# old_line_kick.net
KiCad netlist of a schematic drawn in EAGLE
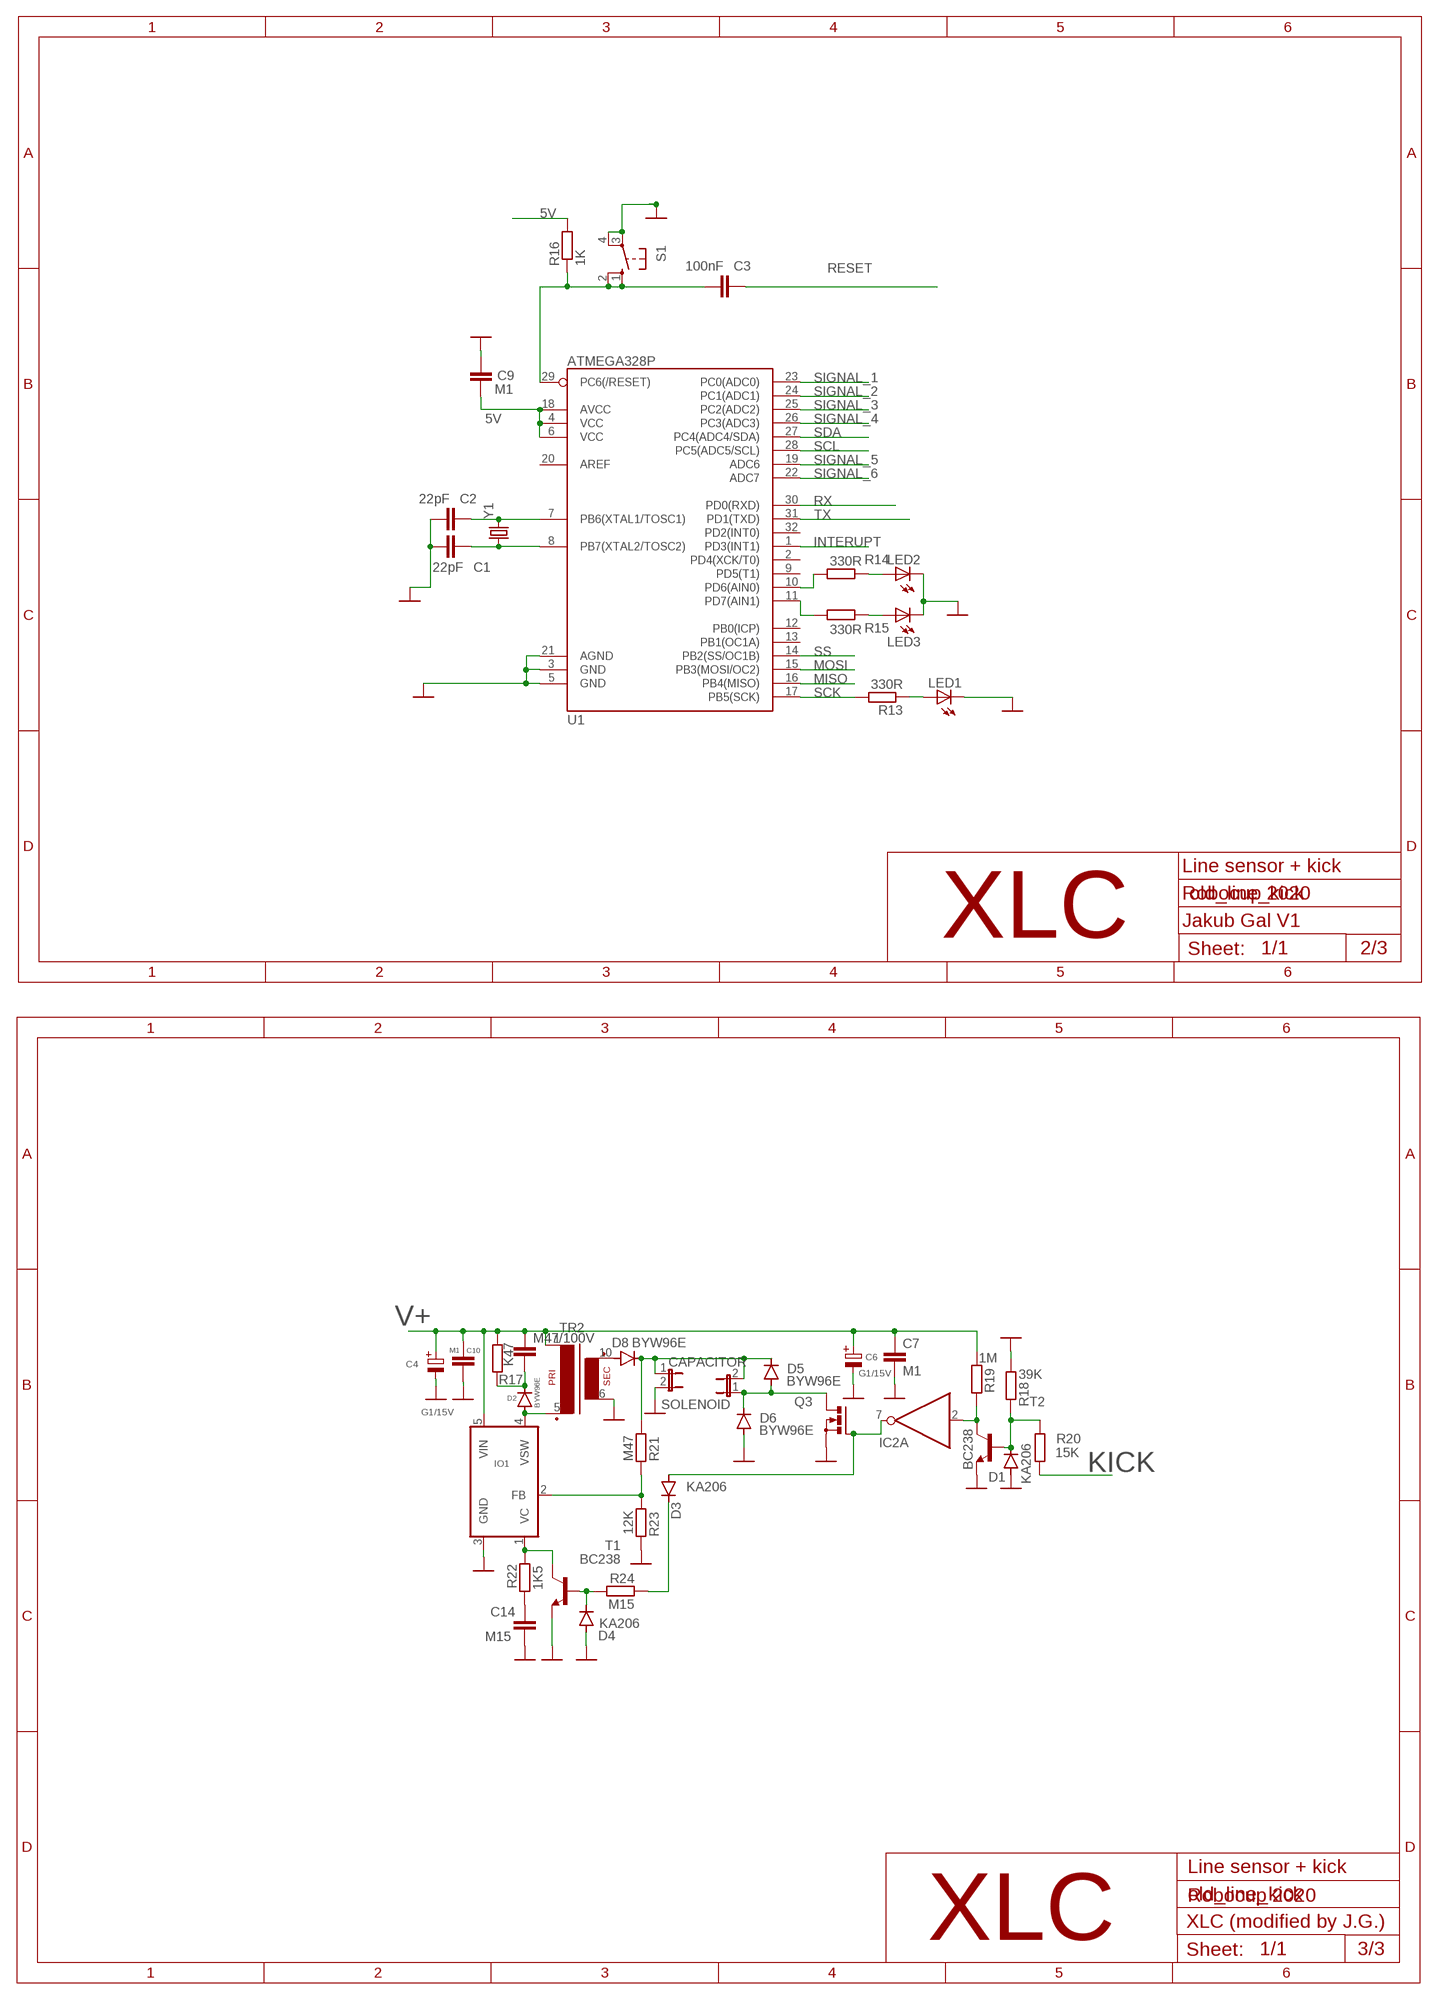
[diagram p0: schematic, sheet 1, part 1 of 2]
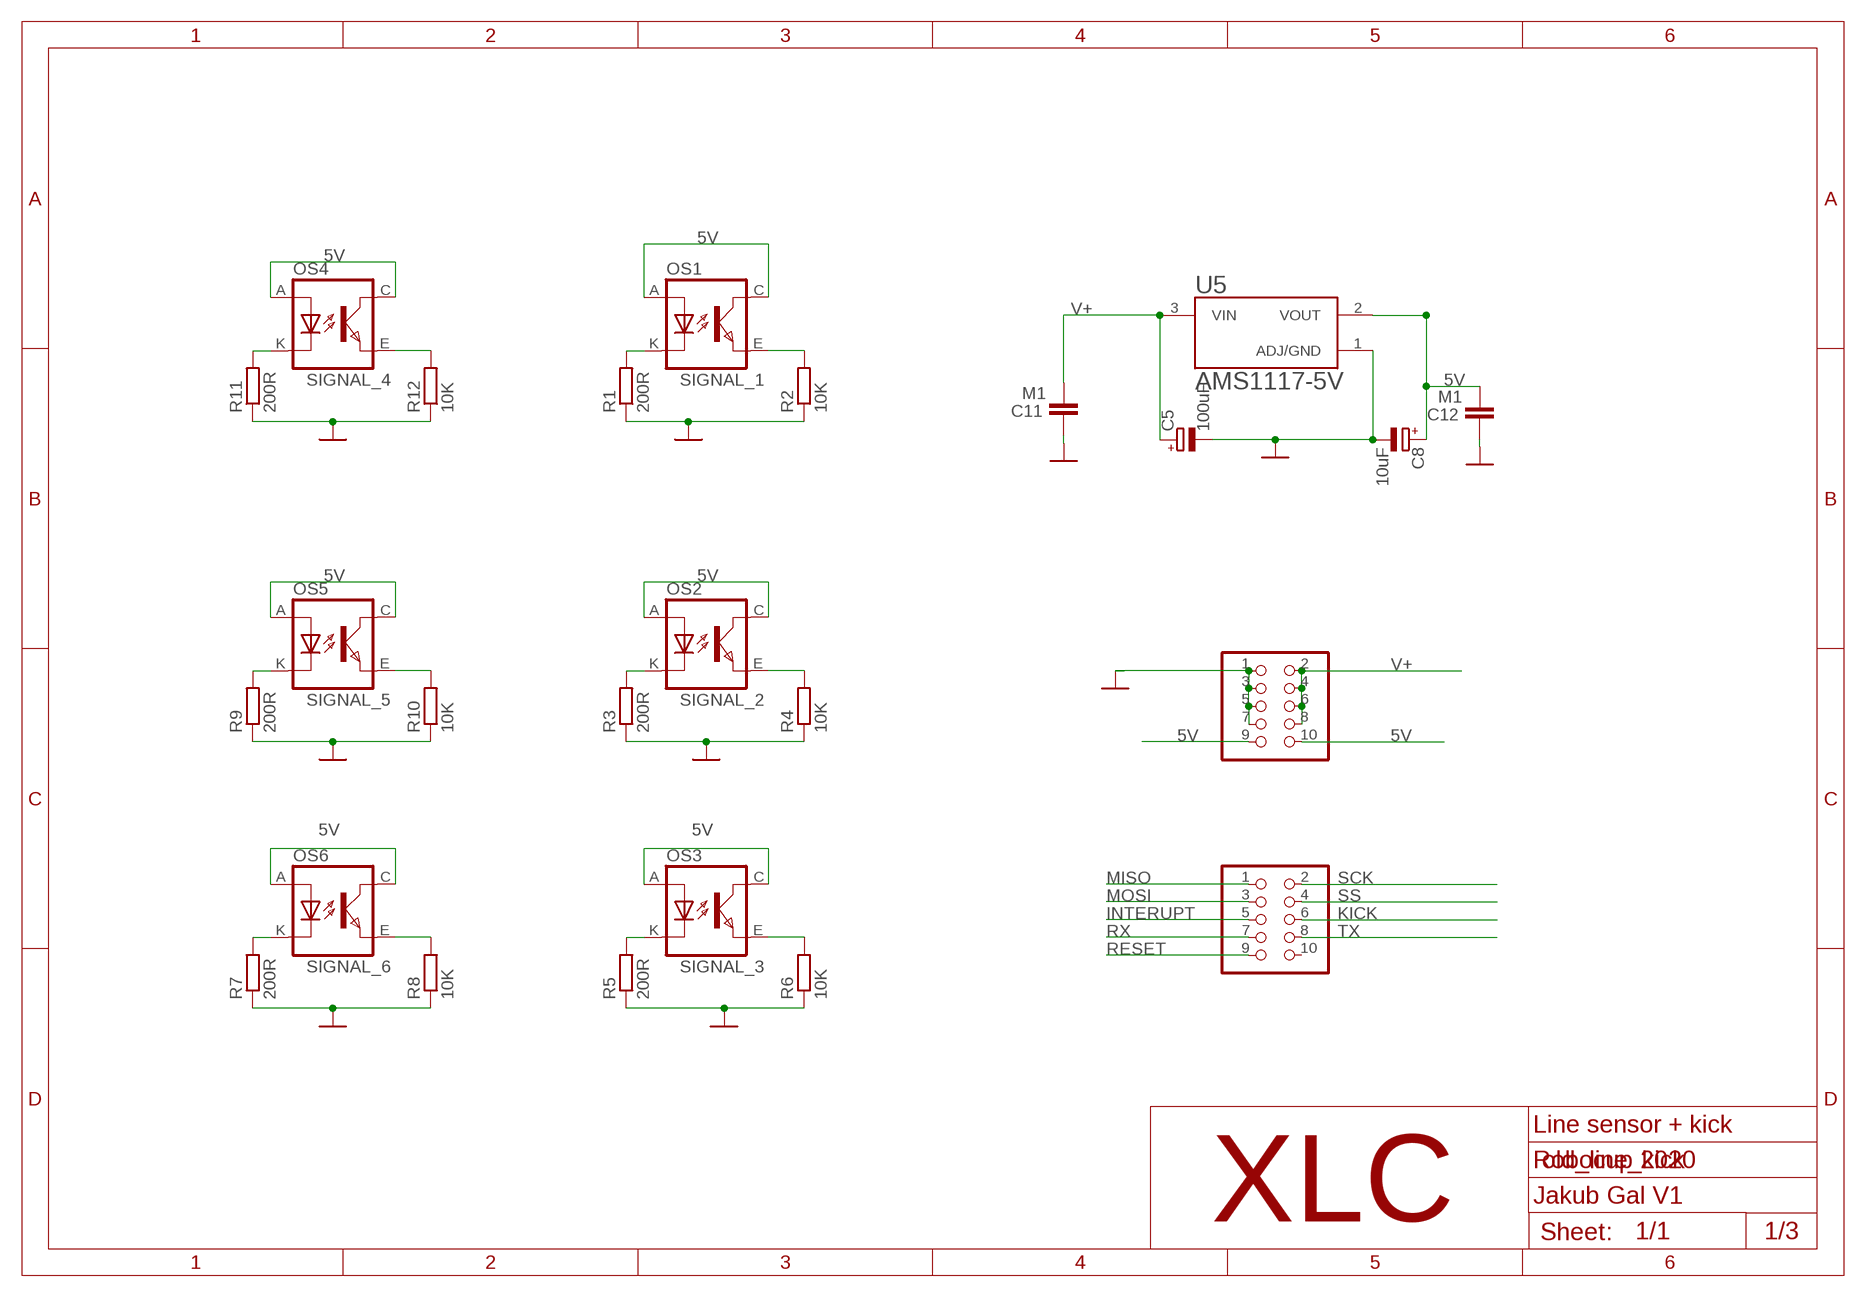
[diagram p1: schematic, sheet 1, part 2 of 2]

(export (version "E")
  (design (tool "Eeschema 10.0.6"))
  (components
    (comp (ref "C1")
      (value "22pF")
      (footprint "eagle-import:C0603")
      (libsource (lib "eagle-import") (part "C-EUC0603"))
    )
    (comp (ref "C2")
      (value "22pF")
      (footprint "eagle-import:C0603")
      (libsource (lib "eagle-import") (part "C-EUC0603"))
    )
    (comp (ref "C3")
      (value "100nF")
      (footprint "eagle-import:C0603")
      (libsource (lib "eagle-import") (part "C-EUC0603"))
    )
    (comp (ref "C4")
      (value "G1/15V")
      (footprint "eagle-import:E-2,5_7-RAD")
      (libsource (lib "eagle-import") (part "KOND-ELEKT-2,5/7"))
    )
    (comp (ref "C5")
      (value "100uF")
      (footprint "eagle-import:UD-6,3X7,7_NICHICON")
      (libsource (lib "eagle-import") (part "CPOL-EUUD-6,3X7,7"))
    )
    (comp (ref "C6")
      (value "G1/15V")
      (footprint "eagle-import:E-2,5_7-RAD")
      (libsource (lib "eagle-import") (part "KOND-ELEKT-2,5/7"))
    )
    (comp (ref "C7")
      (value "M1")
      (footprint "eagle-import:C0805K")
      (libsource (lib "eagle-import") (part "resistor_C-EUC0805K"))
    )
    (comp (ref "C8")
      (value "10uF")
      (footprint "eagle-import:UD-4X5,8_NICHICON")
      (libsource (lib "eagle-import") (part "CPOL-EUUD-4X5,8"))
    )
    (comp (ref "C9")
      (value "M1")
      (footprint "eagle-import:C0603")
      (libsource (lib "eagle-import") (part "C-EUC0603"))
    )
    (comp (ref "C10")
      (value "M1")
      (footprint "eagle-import:C0805K")
      (libsource (lib "eagle-import") (part "resistor_C-EUC0805K"))
    )
    (comp (ref "C11")
      (value "M1")
      (footprint "eagle-import:C0603")
      (libsource (lib "eagle-import") (part "C-EUC0603"))
    )
    (comp (ref "C12")
      (value "M1")
      (footprint "eagle-import:C0603")
      (libsource (lib "eagle-import") (part "C-EUC0603"))
    )
    (comp (ref "C14")
      (value "M15")
      (footprint "eagle-import:C0805K")
      (libsource (lib "eagle-import") (part "resistor_C-EUC0805K"))
    )
    (comp (ref "CAPACITOR")
      (value "JP1E")
      (footprint "eagle-import:JP1")
      (libsource (lib "eagle-import") (part "JP1E"))
    )
    (comp (ref "D1")
      (value "KA206")
      (footprint "eagle-import:D-7.5")
      (libsource (lib "eagle-import") (part "DIODE-D-7.5"))
    )
    (comp (ref "D2")
      (value "BYW96E")
      (footprint "eagle-import:SOD64-10")
      (libsource (lib "eagle-import") (part "BYW96"))
    )
    (comp (ref "D3")
      (value "KA206")
      (footprint "eagle-import:D-7.5")
      (libsource (lib "eagle-import") (part "DIODE-D-7.5"))
    )
    (comp (ref "D4")
      (value "KA206")
      (footprint "eagle-import:D-7.5")
      (libsource (lib "eagle-import") (part "DIODE-D-7.5"))
    )
    (comp (ref "D5")
      (value "BYW96E")
      (footprint "eagle-import:SOD64-10")
      (libsource (lib "eagle-import") (part "BYW96"))
    )
    (comp (ref "D6")
      (value "BYW96E")
      (footprint "eagle-import:SOD64-10")
      (libsource (lib "eagle-import") (part "BYW96"))
    )
    (comp (ref "D8")
      (value "BYW96E")
      (footprint "eagle-import:SOD64-10")
      (libsource (lib "eagle-import") (part "BYW96"))
    )
    (comp (ref "IC2")
      (value "MIC4423BM")
      (footprint "eagle-import:SO08")
      (libsource (lib "eagle-import") (part "MIC4423BM"))
    )
    (comp (ref "IO1")
      (value "LT1071V")
      (footprint "eagle-import:TO220-5P")
      (libsource (lib "eagle-import") (part "LT1071V"))
    )
    (comp (ref "JP2")
      (value "PINHD-2X5")
      (footprint "eagle-import:2X05")
      (libsource (lib "eagle-import") (part "PINHD-2X5"))
    )
    (comp (ref "JP3")
      (value "PINHD-2X5")
      (footprint "eagle-import:2X05")
      (libsource (lib "eagle-import") (part "PINHD-2X5"))
    )
    (comp (ref "LED1")
      (value "LEDCHIPLED_0603")
      (footprint "eagle-import:CHIPLED_0603")
      (libsource (lib "eagle-import") (part "LEDCHIPLED_0603"))
    )
    (comp (ref "LED2")
      (value "LEDCHIPLED_0603")
      (footprint "eagle-import:CHIPLED_0603")
      (libsource (lib "eagle-import") (part "LEDCHIPLED_0603"))
    )
    (comp (ref "LED3")
      (value "LEDCHIPLED_0603")
      (footprint "eagle-import:CHIPLED_0603")
      (libsource (lib "eagle-import") (part "LEDCHIPLED_0603"))
    )
    (comp (ref "M47/100V")
      (value "C-EUC0805K")
      (footprint "eagle-import:C0805K")
      (libsource (lib "eagle-import") (part "resistor_C-EUC0805K"))
    )
    (comp (ref "OS1")
      (value "TCRT5000")
      (footprint "eagle-import:TCRT5000")
      (libsource (lib "eagle-import") (part "TCRT5000"))
    )
    (comp (ref "OS2")
      (value "TCRT5000")
      (footprint "eagle-import:TCRT5000")
      (libsource (lib "eagle-import") (part "TCRT5000"))
    )
    (comp (ref "OS3")
      (value "TCRT5000")
      (footprint "eagle-import:TCRT5000")
      (libsource (lib "eagle-import") (part "TCRT5000"))
    )
    (comp (ref "OS4")
      (value "TCRT5000")
      (footprint "eagle-import:TCRT5000")
      (fields (field (name "SPICEPREFIX") "O"))
      (libsource (lib "eagle-import") (part "TCRT5000"))
    )
    (comp (ref "OS5")
      (value "TCRT5000")
      (footprint "eagle-import:TCRT5000")
      (libsource (lib "eagle-import") (part "TCRT5000"))
    )
    (comp (ref "OS6")
      (value "TCRT5000")
      (footprint "eagle-import:TCRT5000")
      (fields (field (name "SPICEPREFIX") "O"))
      (libsource (lib "eagle-import") (part "TCRT5000"))
    )
    (comp (ref "Q3")
      (value "PMOSFET_NTO220BV")
      (footprint "eagle-import:TO220BV")
      (libsource (lib "eagle-import") (part "PMOSFET_NTO220BV"))
    )
    (comp (ref "R1")
      (value "200R")
      (footprint "eagle-import:R0603")
      (libsource (lib "eagle-import") (part "R-EU_R0603"))
    )
    (comp (ref "R2")
      (value "10K")
      (footprint "eagle-import:R0603")
      (libsource (lib "eagle-import") (part "R-EU_R0603"))
    )
    (comp (ref "R3")
      (value "200R")
      (footprint "eagle-import:R0603")
      (libsource (lib "eagle-import") (part "R-EU_R0603"))
    )
    (comp (ref "R4")
      (value "10K")
      (footprint "eagle-import:R0603")
      (libsource (lib "eagle-import") (part "R-EU_R0603"))
    )
    (comp (ref "R5")
      (value "200R")
      (footprint "eagle-import:R0603")
      (libsource (lib "eagle-import") (part "R-EU_R0603"))
    )
    (comp (ref "R6")
      (value "10K")
      (footprint "eagle-import:R0603")
      (libsource (lib "eagle-import") (part "R-EU_R0603"))
    )
    (comp (ref "R7")
      (value "200R")
      (footprint "eagle-import:R0603")
      (libsource (lib "eagle-import") (part "R-EU_R0603"))
    )
    (comp (ref "R8")
      (value "10K")
      (footprint "eagle-import:R0603")
      (libsource (lib "eagle-import") (part "R-EU_R0603"))
    )
    (comp (ref "R9")
      (value "200R")
      (footprint "eagle-import:R0603")
      (libsource (lib "eagle-import") (part "R-EU_R0603"))
    )
    (comp (ref "R10")
      (value "10K")
      (footprint "eagle-import:R0603")
      (libsource (lib "eagle-import") (part "R-EU_R0603"))
    )
    (comp (ref "R11")
      (value "200R")
      (footprint "eagle-import:R0603")
      (libsource (lib "eagle-import") (part "R-EU_R0603"))
    )
    (comp (ref "R12")
      (value "10K")
      (footprint "eagle-import:R0603")
      (libsource (lib "eagle-import") (part "R-EU_R0603"))
    )
    (comp (ref "R13")
      (value "330R")
      (footprint "eagle-import:R0603")
      (libsource (lib "eagle-import") (part "R-EU_R0603"))
    )
    (comp (ref "R14")
      (value "330R")
      (footprint "eagle-import:R0603")
      (libsource (lib "eagle-import") (part "R-EU_R0603"))
    )
    (comp (ref "R15")
      (value "330R")
      (footprint "eagle-import:R0603")
      (libsource (lib "eagle-import") (part "R-EU_R0603"))
    )
    (comp (ref "R16")
      (value "1K")
      (footprint "eagle-import:R0603")
      (libsource (lib "eagle-import") (part "R-EU_R0603"))
    )
    (comp (ref "R17")
      (value "K47")
      (footprint "eagle-import:R0603")
      (libsource (lib "eagle-import") (part "resistor_R-EU_R0603"))
    )
    (comp (ref "R18")
      (value "39K")
      (footprint "eagle-import:R0603")
      (libsource (lib "eagle-import") (part "resistor_R-EU_R0603"))
    )
    (comp (ref "R19")
      (value "1M")
      (footprint "eagle-import:R0603")
      (libsource (lib "eagle-import") (part "resistor_R-EU_R0603"))
    )
    (comp (ref "R20")
      (value "15K")
      (footprint "eagle-import:R0603")
      (libsource (lib "eagle-import") (part "resistor_R-EU_R0603"))
    )
    (comp (ref "R21")
      (value "M47")
      (footprint "eagle-import:R0603")
      (libsource (lib "eagle-import") (part "resistor_R-EU_R0603"))
    )
    (comp (ref "R22")
      (value "1K5")
      (footprint "eagle-import:R0603")
      (libsource (lib "eagle-import") (part "resistor_R-EU_R0603"))
    )
    (comp (ref "R23")
      (value "12K")
      (footprint "eagle-import:R0603")
      (libsource (lib "eagle-import") (part "resistor_R-EU_R0603"))
    )
    (comp (ref "R24")
      (value "M15")
      (footprint "eagle-import:R0603")
      (libsource (lib "eagle-import") (part "resistor_R-EU_R0603"))
    )
    (comp (ref "S1")
      (value "10-XX")
      (footprint "eagle-import:B3F-10XX")
      (fields (field (name "MPN") "B3F-1000"))
      (libsource (lib "eagle-import") (part "10-XX"))
    )
    (comp (ref "SOLENOID")
      (value "JP1E")
      (footprint "eagle-import:JP1")
      (libsource (lib "eagle-import") (part "JP1E"))
    )
    (comp (ref "T1")
      (value "BC238")
      (footprint "eagle-import:TO92")
      (libsource (lib "eagle-import") (part "BC238"))
    )
    (comp (ref "T2")
      (value "BC238")
      (footprint "eagle-import:TO92")
      (libsource (lib "eagle-import") (part "BC238"))
    )
    (comp (ref "TR2")
      (value "TRAFO-E10-R\"\"")
      (footprint "eagle-import:TRAFO-EE17X20")
      (libsource (lib "eagle-import") (part "TRAFO-E10-R{dblquote}{dblquote}"))
    )
    (comp (ref "U1")
      (value "ATMEGA328P")
      (footprint "eagle-import:TQFP32-08")
      (libsource (lib "eagle-import") (part "ATMEGA328_SMT"))
    )
    (comp (ref "U5")
      (value "AMS1117-5V")
      (footprint "eagle-import:SOT229P700X180-4N")
      (fields (field (name "MF") "Advanced Monolithic Systems") (field (name "MP") "AMS1117-3.3"))
      (libsource (lib "eagle-import") (part "AMS1117-3.3"))
    )
    (comp (ref "Y1")
      (value "CRYSTALHC49US")
      (footprint "eagle-import:HC49US")
      (libsource (lib "eagle-import") (part "CRYSTALHC49US"))
    )
  )
  (nets
    (net (code "1") (name "/5V") (class "Default")
      (node (ref "C12") (pin "1") (pinfunction "1_1") (pintype "passive"))
      (node (ref "C8") (pin "+") (pinfunction "+_+") (pintype "passive"))
      (node (ref "C9") (pin "1") (pinfunction "1_1") (pintype "passive"))
      (node (ref "JP3") (pin "10") (pinfunction "10_10") (pintype "passive"))
      (node (ref "JP3") (pin "9") (pinfunction "9_9") (pintype "passive"))
      (node (ref "OS1") (pin "A") (pinfunction "ANODE_A") (pintype "passive"))
      (node (ref "OS1") (pin "C") (pinfunction "COLLECTOR_C") (pintype "passive"))
      (node (ref "OS2") (pin "A") (pinfunction "ANODE_A") (pintype "passive"))
      (node (ref "OS2") (pin "C") (pinfunction "COLLECTOR_C") (pintype "passive"))
      (node (ref "OS3") (pin "A") (pinfunction "ANODE_A") (pintype "passive"))
      (node (ref "OS3") (pin "C") (pinfunction "COLLECTOR_C") (pintype "passive"))
      (node (ref "OS4") (pin "A") (pinfunction "ANODE_A") (pintype "passive"))
      (node (ref "OS4") (pin "C") (pinfunction "COLLECTOR_C") (pintype "passive"))
      (node (ref "OS5") (pin "A") (pinfunction "ANODE_A") (pintype "passive"))
      (node (ref "OS5") (pin "C") (pinfunction "COLLECTOR_C") (pintype "passive"))
      (node (ref "OS6") (pin "A") (pinfunction "ANODE_A") (pintype "passive"))
      (node (ref "OS6") (pin "C") (pinfunction "COLLECTOR_C") (pintype "passive"))
      (node (ref "R16") (pin "2") (pinfunction "2_2") (pintype "passive"))
      (node (ref "U1") (pin "18") (pinfunction "AVCC_18") (pintype "bidirectional"))
      (node (ref "U1") (pin "4") (pinfunction "VCC_4") (pintype "bidirectional"))
      (node (ref "U1") (pin "6") (pinfunction "VCC_6") (pintype "bidirectional"))
      (node (ref "U5") (pin "2") (pinfunction "VOUT_2") (pintype "output"))
    )
    (net (code "2") (name "/INTERUPT") (class "Default")
      (node (ref "JP2") (pin "5") (pinfunction "5_5") (pintype "passive"))
      (node (ref "U1") (pin "1") (pinfunction "PD3(INT1)_1") (pintype "bidirectional"))
    )
    (net (code "3") (name "/KICK") (class "Default")
      (node (ref "JP2") (pin "6") (pinfunction "6_6") (pintype "passive"))
      (node (ref "R20") (pin "1") (pinfunction "1_1") (pintype "passive"))
    )
    (net (code "4") (name "/MISO") (class "Default")
      (node (ref "JP2") (pin "1") (pinfunction "1_1") (pintype "passive"))
      (node (ref "U1") (pin "16") (pinfunction "PB4(MISO)_16") (pintype "bidirectional"))
    )
    (net (code "5") (name "/MOSI") (class "Default")
      (node (ref "JP2") (pin "3") (pinfunction "3_3") (pintype "passive"))
      (node (ref "U1") (pin "15") (pinfunction "PB3(MOSI/OC2)_15") (pintype "bidirectional"))
    )
    (net (code "6") (name "/RESET") (class "Default")
      (node (ref "C3") (pin "2") (pinfunction "2_2") (pintype "passive"))
      (node (ref "JP2") (pin "9") (pinfunction "9_9") (pintype "passive"))
    )
    (net (code "7") (name "/RX") (class "Default")
      (node (ref "JP2") (pin "7") (pinfunction "7_7") (pintype "passive"))
      (node (ref "U1") (pin "30") (pinfunction "PD0(RXD)_30") (pintype "bidirectional"))
    )
    (net (code "8") (name "/SCK") (class "Default")
      (node (ref "JP2") (pin "2") (pinfunction "2_2") (pintype "passive"))
      (node (ref "R13") (pin "2") (pinfunction "2_2") (pintype "passive"))
      (node (ref "U1") (pin "17") (pinfunction "PB5(SCK)_17") (pintype "bidirectional"))
    )
    (net (code "9") (name "/SCL") (class "Default")
      (node (ref "U1") (pin "28") (pinfunction "PC5(ADC5/SCL)_28") (pintype "bidirectional"))
    )
    (net (code "10") (name "/SDA") (class "Default")
      (node (ref "U1") (pin "27") (pinfunction "PC4(ADC4/SDA)_27") (pintype "bidirectional"))
    )
    (net (code "11") (name "/SIGNAL_1") (class "Default")
      (node (ref "OS1") (pin "E") (pinfunction "EMITTER_E") (pintype "passive"))
      (node (ref "R2") (pin "2") (pinfunction "2_2") (pintype "passive"))
      (node (ref "U1") (pin "23") (pinfunction "PC0(ADC0)_23") (pintype "bidirectional"))
    )
    (net (code "12") (name "/SIGNAL_2") (class "Default")
      (node (ref "OS2") (pin "E") (pinfunction "EMITTER_E") (pintype "passive"))
      (node (ref "R4") (pin "2") (pinfunction "2_2") (pintype "passive"))
      (node (ref "U1") (pin "24") (pinfunction "PC1(ADC1)_24") (pintype "bidirectional"))
    )
    (net (code "13") (name "/SIGNAL_3") (class "Default")
      (node (ref "OS3") (pin "E") (pinfunction "EMITTER_E") (pintype "passive"))
      (node (ref "R6") (pin "2") (pinfunction "2_2") (pintype "passive"))
      (node (ref "U1") (pin "25") (pinfunction "PC2(ADC2)_25") (pintype "bidirectional"))
    )
    (net (code "14") (name "/SIGNAL_4") (class "Default")
      (node (ref "OS4") (pin "E") (pinfunction "EMITTER_E") (pintype "passive"))
      (node (ref "R12") (pin "2") (pinfunction "2_2") (pintype "passive"))
      (node (ref "U1") (pin "26") (pinfunction "PC3(ADC3)_26") (pintype "bidirectional"))
    )
    (net (code "15") (name "/SIGNAL_5") (class "Default")
      (node (ref "OS5") (pin "E") (pinfunction "EMITTER_E") (pintype "passive"))
      (node (ref "R10") (pin "2") (pinfunction "2_2") (pintype "passive"))
      (node (ref "U1") (pin "19") (pinfunction "ADC6_19") (pintype "bidirectional"))
    )
    (net (code "16") (name "/SIGNAL_6") (class "Default")
      (node (ref "OS6") (pin "E") (pinfunction "EMITTER_E") (pintype "passive"))
      (node (ref "R8") (pin "2") (pinfunction "2_2") (pintype "passive"))
      (node (ref "U1") (pin "22") (pinfunction "ADC7_22") (pintype "bidirectional"))
    )
    (net (code "17") (name "/SS") (class "Default")
      (node (ref "JP2") (pin "4") (pinfunction "4_4") (pintype "passive"))
      (node (ref "U1") (pin "14") (pinfunction "PB2(SS/OC1B)_14") (pintype "bidirectional"))
    )
    (net (code "18") (name "/TX") (class "Default")
      (node (ref "JP2") (pin "8") (pinfunction "8_8") (pintype "passive"))
      (node (ref "U1") (pin "31") (pinfunction "PD1(TXD)_31") (pintype "bidirectional"))
    )
    (net (code "19") (name "/V+") (class "Default")
      (node (ref "C10") (pin "1") (pinfunction "1_1") (pintype "passive"))
      (node (ref "C11") (pin "1") (pinfunction "1_1") (pintype "passive"))
      (node (ref "C4") (pin "+") (pinfunction "+_+") (pintype "passive"))
      (node (ref "C5") (pin "+") (pinfunction "+_+") (pintype "passive"))
      (node (ref "C6") (pin "+") (pinfunction "+_+") (pintype "passive"))
      (node (ref "C7") (pin "1") (pinfunction "1_1") (pintype "passive"))
      (node (ref "IO1") (pin "5") (pinfunction "VIN_5") (pintype "power_in"))
      (node (ref "JP3") (pin "2") (pinfunction "2_2") (pintype "passive"))
      (node (ref "JP3") (pin "4") (pinfunction "4_4") (pintype "passive"))
      (node (ref "JP3") (pin "6") (pinfunction "6_6") (pintype "passive"))
      (node (ref "JP3") (pin "8") (pinfunction "8_8") (pintype "passive"))
      (node (ref "M47/100V") (pin "1") (pinfunction "1_1") (pintype "passive"))
      (node (ref "R17") (pin "1") (pinfunction "1_1") (pintype "passive"))
      (node (ref "R19") (pin "2") (pinfunction "2_2") (pintype "passive"))
      (node (ref "TR2") (pin "1") (pinfunction "1_1") (pintype "passive"))
      (node (ref "U5") (pin "3") (pinfunction "VIN_3") (pintype "input"))
    )
    (net (code "20") (name "GND") (class "Default")
      (node (ref "C1") (pin "1") (pinfunction "1_1") (pintype "passive"))
      (node (ref "C10") (pin "2") (pinfunction "2_2") (pintype "passive"))
      (node (ref "C11") (pin "2") (pinfunction "2_2") (pintype "passive"))
      (node (ref "C12") (pin "2") (pinfunction "2_2") (pintype "passive"))
      (node (ref "C14") (pin "2") (pinfunction "2_2") (pintype "passive"))
      (node (ref "C2") (pin "1") (pinfunction "1_1") (pintype "passive"))
      (node (ref "C4") (pin "-") (pinfunction "-_-") (pintype "passive"))
      (node (ref "C5") (pin "-") (pinfunction "-_-") (pintype "passive"))
      (node (ref "C6") (pin "-") (pinfunction "-_-") (pintype "passive"))
      (node (ref "C7") (pin "2") (pinfunction "2_2") (pintype "passive"))
      (node (ref "C8") (pin "-") (pinfunction "-_-") (pintype "passive"))
      (node (ref "C9") (pin "2") (pinfunction "2_2") (pintype "passive"))
      (node (ref "CAPACITOR") (pin "2") (pinfunction "2_2") (pintype "passive"))
      (node (ref "D1") (pin "A") (pinfunction "A_A") (pintype "passive"))
      (node (ref "D4") (pin "A") (pinfunction "A_A") (pintype "passive"))
      (node (ref "D6") (pin "A") (pinfunction "A_A") (pintype "passive"))
      (node (ref "IO1") (pin "3") (pinfunction "GND_3") (pintype "power_in"))
      (node (ref "JP3") (pin "1") (pinfunction "1_1") (pintype "passive"))
      (node (ref "JP3") (pin "3") (pinfunction "3_3") (pintype "passive"))
      (node (ref "JP3") (pin "5") (pinfunction "5_5") (pintype "passive"))
      (node (ref "JP3") (pin "7") (pinfunction "7_7") (pintype "passive"))
      (node (ref "LED1") (pin "C") (pinfunction "C_C") (pintype "passive"))
      (node (ref "LED2") (pin "C") (pinfunction "C_C") (pintype "passive"))
      (node (ref "LED3") (pin "C") (pinfunction "C_C") (pintype "passive"))
      (node (ref "Q3") (pin "S") (pinfunction "S_S") (pintype "passive"))
      (node (ref "R1") (pin "1") (pinfunction "1_1") (pintype "passive"))
      (node (ref "R10") (pin "1") (pinfunction "1_1") (pintype "passive"))
      (node (ref "R11") (pin "1") (pinfunction "1_1") (pintype "passive"))
      (node (ref "R12") (pin "1") (pinfunction "1_1") (pintype "passive"))
      (node (ref "R18") (pin "2") (pinfunction "2_2") (pintype "passive"))
      (node (ref "R2") (pin "1") (pinfunction "1_1") (pintype "passive"))
      (node (ref "R23") (pin "1") (pinfunction "1_1") (pintype "passive"))
      (node (ref "R3") (pin "1") (pinfunction "1_1") (pintype "passive"))
      (node (ref "R4") (pin "1") (pinfunction "1_1") (pintype "passive"))
      (node (ref "R5") (pin "1") (pinfunction "1_1") (pintype "passive"))
      (node (ref "R6") (pin "1") (pinfunction "1_1") (pintype "passive"))
      (node (ref "R7") (pin "1") (pinfunction "1_1") (pintype "passive"))
      (node (ref "R8") (pin "1") (pinfunction "1_1") (pintype "passive"))
      (node (ref "R9") (pin "1") (pinfunction "1_1") (pintype "passive"))
      (node (ref "S1") (pin "3") (pinfunction "P_3") (pintype "passive"))
      (node (ref "S1") (pin "4") (pinfunction "P1_4") (pintype "passive"))
      (node (ref "T1") (pin "1") (pinfunction "E_1") (pintype "passive"))
      (node (ref "T2") (pin "1") (pinfunction "E_1") (pintype "passive"))
      (node (ref "TR2") (pin "6") (pinfunction "3_6") (pintype "passive"))
      (node (ref "U1") (pin "21") (pinfunction "AGND_21") (pintype "bidirectional"))
      (node (ref "U1") (pin "3") (pinfunction "GND_3") (pintype "bidirectional"))
      (node (ref "U1") (pin "5") (pinfunction "GND_5") (pintype "bidirectional"))
      (node (ref "U5") (pin "1") (pinfunction "ADJ/GND_1") (pintype "power_in"))
    )
    (net (code "21") (name "Net-(C14-Pad1)") (class "Default")
      (node (ref "C14") (pin "1") (pinfunction "1_1") (pintype "passive"))
      (node (ref "R22") (pin "2") (pinfunction "2_2") (pintype "passive"))
    )
    (net (code "22") (name "Net-(CAPACITOR-Pad1)") (class "Default")
      (node (ref "CAPACITOR") (pin "1") (pinfunction "1_1") (pintype "passive"))
      (node (ref "D5") (pin "C") (pinfunction "C_C") (pintype "passive"))
      (node (ref "D8") (pin "C") (pinfunction "C_C") (pintype "passive"))
      (node (ref "R21") (pin "2") (pinfunction "2_2") (pintype "passive"))
      (node (ref "SOLENOID") (pin "2") (pinfunction "2_2") (pintype "passive"))
    )
    (net (code "23") (name "Net-(D2-PadC)") (class "Default")
      (node (ref "D2") (pin "C") (pinfunction "C_C") (pintype "passive"))
      (node (ref "M47/100V") (pin "2") (pinfunction "2_2") (pintype "passive"))
      (node (ref "R17") (pin "2") (pinfunction "2_2") (pintype "passive"))
    )
    (net (code "24") (name "Net-(D3-PadC)") (class "Default")
      (node (ref "D3") (pin "C") (pinfunction "C_C") (pintype "passive"))
      (node (ref "R24") (pin "1") (pinfunction "1_1") (pintype "passive"))
    )
    (net (code "25") (name "Net-(D5-PadA)") (class "Default")
      (node (ref "D5") (pin "A") (pinfunction "A_A") (pintype "passive"))
      (node (ref "D6") (pin "C") (pinfunction "C_C") (pintype "passive"))
      (node (ref "Q3") (pin "D") (pinfunction "D_D") (pintype "passive"))
      (node (ref "SOLENOID") (pin "1") (pinfunction "1_1") (pintype "passive"))
    )
    (net (code "26") (name "Net-(IC2A-IN)") (class "Default")
      (node (ref "IC2") (pin "2") (pinfunction "IN_2") (pintype "input"))
      (node (ref "R19") (pin "1") (pinfunction "1_1") (pintype "passive"))
      (node (ref "T2") (pin "3") (pinfunction "C_3") (pintype "passive"))
    )
    (net (code "27") (name "Net-(IC2A-OUT)") (class "Default")
      (node (ref "D3") (pin "A") (pinfunction "A_A") (pintype "passive"))
      (node (ref "IC2") (pin "7") (pinfunction "OUT_7") (pintype "output"))
      (node (ref "Q3") (pin "G") (pinfunction "G_G") (pintype "passive"))
    )
    (net (code "28") (name "Net-(IO1-FB)") (class "Default")
      (node (ref "IO1") (pin "2") (pinfunction "FB_2") (pintype "input"))
      (node (ref "R21") (pin "1") (pinfunction "1_1") (pintype "passive"))
      (node (ref "R23") (pin "2") (pinfunction "2_2") (pintype "passive"))
    )
    (net (code "29") (name "Net-(IO1-VC)") (class "Default")
      (node (ref "IO1") (pin "1") (pinfunction "VC_1") (pintype "input"))
      (node (ref "R22") (pin "1") (pinfunction "1_1") (pintype "passive"))
      (node (ref "T1") (pin "3") (pinfunction "C_3") (pintype "passive"))
    )
    (net (code "30") (name "Net-(IO1-VSW)") (class "Default")
      (node (ref "D2") (pin "A") (pinfunction "A_A") (pintype "passive"))
      (node (ref "IO1") (pin "4") (pinfunction "VSW_4") (pintype "output"))
      (node (ref "TR2") (pin "5") (pinfunction "2_5") (pintype "passive"))
    )
    (net (code "31") (name "Net-(LED1-PadA)") (class "Default")
      (node (ref "LED1") (pin "A") (pinfunction "A_A") (pintype "passive"))
      (node (ref "R13") (pin "1") (pinfunction "1_1") (pintype "passive"))
    )
    (net (code "32") (name "Net-(LED2-PadA)") (class "Default")
      (node (ref "LED2") (pin "A") (pinfunction "A_A") (pintype "passive"))
      (node (ref "R14") (pin "1") (pinfunction "1_1") (pintype "passive"))
    )
    (net (code "33") (name "Net-(LED3-PadA)") (class "Default")
      (node (ref "LED3") (pin "A") (pinfunction "A_A") (pintype "passive"))
      (node (ref "R15") (pin "1") (pinfunction "1_1") (pintype "passive"))
    )
    (net (code "34") (name "Net-(OS1-CATHODE)") (class "Default")
      (node (ref "OS1") (pin "K") (pinfunction "CATHODE_K") (pintype "passive"))
      (node (ref "R1") (pin "2") (pinfunction "2_2") (pintype "passive"))
    )
    (net (code "35") (name "Net-(OS2-CATHODE)") (class "Default")
      (node (ref "OS2") (pin "K") (pinfunction "CATHODE_K") (pintype "passive"))
      (node (ref "R3") (pin "2") (pinfunction "2_2") (pintype "passive"))
    )
    (net (code "36") (name "Net-(OS3-CATHODE)") (class "Default")
      (node (ref "OS3") (pin "K") (pinfunction "CATHODE_K") (pintype "passive"))
      (node (ref "R5") (pin "2") (pinfunction "2_2") (pintype "passive"))
    )
    (net (code "37") (name "Net-(OS4-CATHODE)") (class "Default")
      (node (ref "OS4") (pin "K") (pinfunction "CATHODE_K") (pintype "passive"))
      (node (ref "R11") (pin "2") (pinfunction "2_2") (pintype "passive"))
    )
    (net (code "38") (name "Net-(OS5-CATHODE)") (class "Default")
      (node (ref "OS5") (pin "K") (pinfunction "CATHODE_K") (pintype "passive"))
      (node (ref "R9") (pin "2") (pinfunction "2_2") (pintype "passive"))
    )
    (net (code "39") (name "Net-(OS6-CATHODE)") (class "Default")
      (node (ref "OS6") (pin "K") (pinfunction "CATHODE_K") (pintype "passive"))
      (node (ref "R7") (pin "2") (pinfunction "2_2") (pintype "passive"))
    )
    (net (code "40") (name "Net-(S1-S)") (class "Default")
      (node (ref "C3") (pin "1") (pinfunction "1_1") (pintype "passive"))
      (node (ref "R16") (pin "1") (pinfunction "1_1") (pintype "passive"))
      (node (ref "S1") (pin "1") (pinfunction "S_1") (pintype "passive"))
      (node (ref "S1") (pin "2") (pinfunction "S1_2") (pintype "passive"))
      (node (ref "U1") (pin "29") (pinfunction "PC6(/RESET)_29") (pintype "bidirectional"))
    )
    (net (code "41") (name "Net-(T1-B)") (class "Default")
      (node (ref "D4") (pin "C") (pinfunction "C_C") (pintype "passive"))
      (node (ref "R24") (pin "2") (pinfunction "2_2") (pintype "passive"))
      (node (ref "T1") (pin "2") (pinfunction "B_2") (pintype "passive"))
    )
    (net (code "42") (name "Net-(T2-B)") (class "Default")
      (node (ref "D1") (pin "C") (pinfunction "C_C") (pintype "passive"))
      (node (ref "R18") (pin "1") (pinfunction "1_1") (pintype "passive"))
      (node (ref "R20") (pin "2") (pinfunction "2_2") (pintype "passive"))
      (node (ref "T2") (pin "2") (pinfunction "B_2") (pintype "passive"))
    )
    (net (code "43") (name "Net-(TR2-4)") (class "Default")
      (node (ref "D8") (pin "A") (pinfunction "A_A") (pintype "passive"))
      (node (ref "TR2") (pin "10") (pinfunction "4_10") (pintype "passive"))
    )
    (net (code "44") (name "Net-(U1-PB6(XTAL1{slash}TOSC1))") (class "Default")
      (node (ref "C2") (pin "2") (pinfunction "2_2") (pintype "passive"))
      (node (ref "U1") (pin "7") (pinfunction "PB6(XTAL1/TOSC1)_7") (pintype "bidirectional"))
      (node (ref "Y1") (pin "2") (pinfunction "2_2") (pintype "passive"))
    )
    (net (code "45") (name "Net-(U1-PB7(XTAL2{slash}TOSC2))") (class "Default")
      (node (ref "C1") (pin "2") (pinfunction "2_2") (pintype "passive"))
      (node (ref "U1") (pin "8") (pinfunction "PB7(XTAL2/TOSC2)_8") (pintype "bidirectional"))
      (node (ref "Y1") (pin "1") (pinfunction "1_1") (pintype "passive"))
    )
    (net (code "46") (name "Net-(U1-PD6(AIN0))") (class "Default")
      (node (ref "R14") (pin "2") (pinfunction "2_2") (pintype "passive"))
      (node (ref "U1") (pin "10") (pinfunction "PD6(AIN0)_10") (pintype "bidirectional"))
    )
    (net (code "47") (name "Net-(U1-PD7(AIN1))") (class "Default")
      (node (ref "R15") (pin "2") (pinfunction "2_2") (pintype "passive"))
      (node (ref "U1") (pin "11") (pinfunction "PD7(AIN1)_11") (pintype "bidirectional"))
    )
    (net (code "48") (name "unconnected-(JP2-Pad10)") (class "Default")
      (node (ref "JP2") (pin "10") (pinfunction "10_10") (pintype "passive"))
    )
    (net (code "49") (name "unconnected-(U1-AREF-Pad20)") (class "Default")
      (node (ref "U1") (pin "20") (pinfunction "AREF_20") (pintype "bidirectional"))
    )
    (net (code "50") (name "unconnected-(U1-PB0(ICP)-Pad12)") (class "Default")
      (node (ref "U1") (pin "12") (pinfunction "PB0(ICP)_12") (pintype "bidirectional"))
    )
    (net (code "51") (name "unconnected-(U1-PB1(OC1A)-Pad13)") (class "Default")
      (node (ref "U1") (pin "13") (pinfunction "PB1(OC1A)_13") (pintype "bidirectional"))
    )
    (net (code "52") (name "unconnected-(U1-PD2(INT0)-Pad32)") (class "Default")
      (node (ref "U1") (pin "32") (pinfunction "PD2(INT0)_32") (pintype "bidirectional"))
    )
    (net (code "53") (name "unconnected-(U1-PD4(XCK{slash}T0)-Pad2)") (class "Default")
      (node (ref "U1") (pin "2") (pinfunction "PD4(XCK/T0)_2") (pintype "bidirectional"))
    )
    (net (code "54") (name "unconnected-(U1-PD5(T1)-Pad9)") (class "Default")
      (node (ref "U1") (pin "9") (pinfunction "PD5(T1)_9") (pintype "bidirectional"))
    )
  )
)
